# untitled.net
KiCad netlist of a schematic drawn in EAGLE
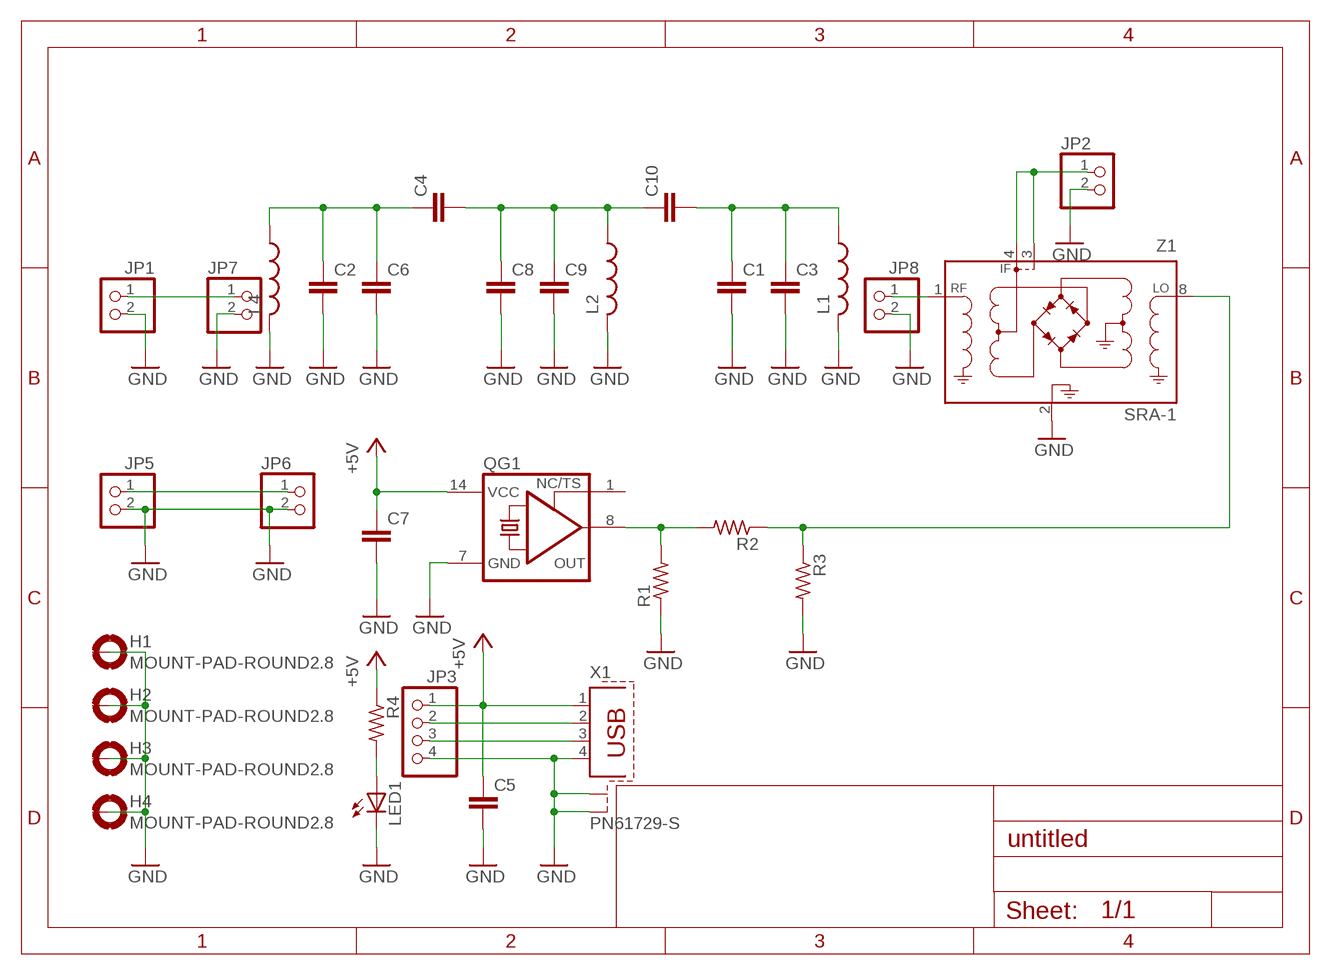
[diagram p0: schematic, sheet 1]

(export (version "E")
  (design (tool "Eeschema 10.0.6"))
  (components
    (comp (ref "C1")
      (value "C5/2.5")
      (footprint "eagle-import:C5B2.5")
      (libsource (lib "eagle-import") (part "C5/2.5"))
    )
    (comp (ref "C2")
      (value "C5/2.5")
      (footprint "eagle-import:C5B2.5")
      (libsource (lib "eagle-import") (part "C5/2.5"))
    )
    (comp (ref "C3")
      (value "C5/2.5")
      (footprint "eagle-import:C5B2.5")
      (libsource (lib "eagle-import") (part "C5/2.5"))
    )
    (comp (ref "C4")
      (value "C5/2.5")
      (footprint "eagle-import:C5B2.5")
      (libsource (lib "eagle-import") (part "C5/2.5"))
    )
    (comp (ref "C5")
      (value "C5/2.5")
      (footprint "eagle-import:C5B2.5")
      (libsource (lib "eagle-import") (part "C5/2.5"))
    )
    (comp (ref "C6")
      (value "C5/2.5")
      (footprint "eagle-import:C5B2.5")
      (libsource (lib "eagle-import") (part "C5/2.5"))
    )
    (comp (ref "C7")
      (value "C5/2.5")
      (footprint "eagle-import:C5B2.5")
      (libsource (lib "eagle-import") (part "C5/2.5"))
    )
    (comp (ref "C8")
      (value "C5/2.5")
      (footprint "eagle-import:C5B2.5")
      (libsource (lib "eagle-import") (part "C5/2.5"))
    )
    (comp (ref "C9")
      (value "C5/2.5")
      (footprint "eagle-import:C5B2.5")
      (libsource (lib "eagle-import") (part "C5/2.5"))
    )
    (comp (ref "C10")
      (value "C5/2.5")
      (footprint "eagle-import:C5B2.5")
      (libsource (lib "eagle-import") (part "C5/2.5"))
    )
    (comp (ref "H1")
      (value "MOUNT-PAD-ROUND2.8")
      (footprint "eagle-import:2,8-PAD")
      (libsource (lib "eagle-import") (part "MOUNT-PAD-ROUND2.8"))
    )
    (comp (ref "H2")
      (value "MOUNT-PAD-ROUND2.8")
      (footprint "eagle-import:2,8-PAD")
      (libsource (lib "eagle-import") (part "MOUNT-PAD-ROUND2.8"))
    )
    (comp (ref "H3")
      (value "MOUNT-PAD-ROUND2.8")
      (footprint "eagle-import:2,8-PAD")
      (libsource (lib "eagle-import") (part "MOUNT-PAD-ROUND2.8"))
    )
    (comp (ref "H4")
      (value "MOUNT-PAD-ROUND2.8")
      (footprint "eagle-import:2,8-PAD")
      (libsource (lib "eagle-import") (part "MOUNT-PAD-ROUND2.8"))
    )
    (comp (ref "JP1")
      (value "PINHD-1X2")
      (footprint "eagle-import:1X02")
      (libsource (lib "eagle-import") (part "PINHD-1X2"))
    )
    (comp (ref "JP2")
      (value "PINHD-1X2")
      (footprint "eagle-import:1X02")
      (libsource (lib "eagle-import") (part "PINHD-1X2"))
    )
    (comp (ref "JP3")
      (value "PINHD-1X4")
      (footprint "eagle-import:1X04")
      (libsource (lib "eagle-import") (part "PINHD-1X4"))
    )
    (comp (ref "JP5")
      (value "PINHD-1X2")
      (footprint "eagle-import:1X02")
      (libsource (lib "eagle-import") (part "PINHD-1X2"))
    )
    (comp (ref "JP6")
      (value "PINHD-1X2")
      (footprint "eagle-import:1X02")
      (libsource (lib "eagle-import") (part "PINHD-1X2"))
    )
    (comp (ref "JP7")
      (value "PINHD-1X2")
      (footprint "eagle-import:1X02")
      (libsource (lib "eagle-import") (part "PINHD-1X2"))
    )
    (comp (ref "JP8")
      (value "PINHD-1X2")
      (footprint "eagle-import:1X02")
      (libsource (lib "eagle-import") (part "PINHD-1X2"))
    )
    (comp (ref "L1")
      (value "L-US0207/7")
      (footprint "eagle-import:0207_7")
      (libsource (lib "eagle-import") (part "L-US0207/7"))
    )
    (comp (ref "L2")
      (value "L-US0207/7")
      (footprint "eagle-import:0207_7")
      (libsource (lib "eagle-import") (part "L-US0207/7"))
    )
    (comp (ref "L4")
      (value "L-US0207/7")
      (footprint "eagle-import:0207_7")
      (libsource (lib "eagle-import") (part "L-US0207/7"))
    )
    (comp (ref "LED1")
      (value "LED3MM")
      (footprint "eagle-import:LED3MM")
      (libsource (lib "eagle-import") (part "LED3MM"))
    )
    (comp (ref "QG1")
      (value "XO-14")
      (footprint "eagle-import:DIL14S")
      (libsource (lib "eagle-import") (part "XO-14"))
    )
    (comp (ref "R1")
      (value "R-US_0207/7")
      (footprint "eagle-import:0207_7")
      (libsource (lib "eagle-import") (part "R-US_0207/7"))
    )
    (comp (ref "R2")
      (value "R-US_0207/7")
      (footprint "eagle-import:0207_7")
      (libsource (lib "eagle-import") (part "R-US_0207/7"))
    )
    (comp (ref "R3")
      (value "R-US_0207/7")
      (footprint "eagle-import:0207_7")
      (libsource (lib "eagle-import") (part "R-US_0207/7"))
    )
    (comp (ref "R4")
      (value "R-US_0207/7")
      (footprint "eagle-import:0207_7")
      (libsource (lib "eagle-import") (part "R-US_0207/7"))
    )
    (comp (ref "X1")
      (value "PN61729-S")
      (footprint "eagle-import:PN61729-S")
      (libsource (lib "eagle-import") (part "PN61729-S"))
    )
    (comp (ref "Z1")
      (value "SRA-1")
      (footprint "eagle-import:A01")
      (libsource (lib "eagle-import") (part "SRA-1"))
    )
  )
  (nets
    (net (code "1") (name "+5V") (class "Default")
      (node (ref "C5") (pin "1") (pinfunction "1_1") (pintype "passive"))
      (node (ref "C7") (pin "1") (pinfunction "1_1") (pintype "passive"))
      (node (ref "JP3") (pin "1") (pinfunction "1_1") (pintype "passive"))
      (node (ref "QG1") (pin "14") (pinfunction "VCC_14") (pintype "power_in"))
      (node (ref "R4") (pin "1") (pinfunction "1_1") (pintype "passive"))
      (node (ref "X1") (pin "1") (pinfunction "1_1") (pintype "passive"))
    )
    (net (code "2") (name "GND") (class "Default")
      (node (ref "C1") (pin "2") (pinfunction "2_2") (pintype "passive"))
      (node (ref "C2") (pin "2") (pinfunction "2_2") (pintype "passive"))
      (node (ref "C3") (pin "2") (pinfunction "2_2") (pintype "passive"))
      (node (ref "C5") (pin "2") (pinfunction "2_2") (pintype "passive"))
      (node (ref "C6") (pin "2") (pinfunction "2_2") (pintype "passive"))
      (node (ref "C7") (pin "2") (pinfunction "2_2") (pintype "passive"))
      (node (ref "C8") (pin "2") (pinfunction "2_2") (pintype "passive"))
      (node (ref "C9") (pin "2") (pinfunction "2_2") (pintype "passive"))
      (node (ref "JP1") (pin "2") (pinfunction "2_2") (pintype "passive"))
      (node (ref "JP2") (pin "2") (pinfunction "2_2") (pintype "passive"))
      (node (ref "JP3") (pin "4") (pinfunction "4_4") (pintype "passive"))
      (node (ref "JP5") (pin "2") (pinfunction "2_2") (pintype "passive"))
      (node (ref "JP6") (pin "2") (pinfunction "2_2") (pintype "passive"))
      (node (ref "JP7") (pin "2") (pinfunction "2_2") (pintype "passive"))
      (node (ref "JP8") (pin "2") (pinfunction "2_2") (pintype "passive"))
      (node (ref "L1") (pin "2") (pinfunction "2_2") (pintype "passive"))
      (node (ref "L2") (pin "2") (pinfunction "2_2") (pintype "passive"))
      (node (ref "L4") (pin "2") (pinfunction "2_2") (pintype "passive"))
      (node (ref "LED1") (pin "K") (pinfunction "C_K") (pintype "passive"))
      (node (ref "QG1") (pin "7") (pinfunction "GND_7") (pintype "power_in"))
      (node (ref "R1") (pin "1") (pinfunction "1_1") (pintype "passive"))
      (node (ref "R3") (pin "2") (pinfunction "2_2") (pintype "passive"))
      (node (ref "X1") (pin "4") (pinfunction "4_4") (pintype "passive"))
      (node (ref "X1") (pin "S1") (pinfunction "S1_S1") (pintype "passive"))
      (node (ref "X1") (pin "S2") (pinfunction "S2_S2") (pintype "passive"))
      (node (ref "Z1") (pin "2") (pinfunction "CASEGROUND_2") (pintype "passive"))
    )
    (net (code "3") (name "Net-(C1-Pad1)") (class "Default")
      (node (ref "C1") (pin "1") (pinfunction "1_1") (pintype "passive"))
      (node (ref "C10") (pin "2") (pinfunction "2_2") (pintype "passive"))
      (node (ref "C3") (pin "1") (pinfunction "1_1") (pintype "passive"))
      (node (ref "L1") (pin "1") (pinfunction "1_1") (pintype "passive"))
    )
    (net (code "4") (name "Net-(C2-Pad1)") (class "Default")
      (node (ref "C2") (pin "1") (pinfunction "1_1") (pintype "passive"))
      (node (ref "C4") (pin "1") (pinfunction "1_1") (pintype "passive"))
      (node (ref "C6") (pin "1") (pinfunction "1_1") (pintype "passive"))
      (node (ref "L4") (pin "1") (pinfunction "1_1") (pintype "passive"))
    )
    (net (code "5") (name "Net-(C10-Pad1)") (class "Default")
      (node (ref "C10") (pin "1") (pinfunction "1_1") (pintype "passive"))
      (node (ref "C4") (pin "2") (pinfunction "2_2") (pintype "passive"))
      (node (ref "C8") (pin "1") (pinfunction "1_1") (pintype "passive"))
      (node (ref "C9") (pin "1") (pinfunction "1_1") (pintype "passive"))
      (node (ref "L2") (pin "1") (pinfunction "1_1") (pintype "passive"))
    )
    (net (code "6") (name "Net-(JP1-Pad1)") (class "Default")
      (node (ref "JP1") (pin "1") (pinfunction "1_1") (pintype "passive"))
      (node (ref "JP7") (pin "1") (pinfunction "1_1") (pintype "passive"))
    )
    (net (code "7") (name "Net-(JP2-Pad1)") (class "Default")
      (node (ref "JP2") (pin "1") (pinfunction "1_1") (pintype "passive"))
      (node (ref "Z1") (pin "3") (pinfunction "IF_3") (pintype "passive"))
      (node (ref "Z1") (pin "4") (pinfunction "IF_4") (pintype "passive"))
    )
    (net (code "8") (name "Net-(JP3-Pad2)") (class "Default")
      (node (ref "JP3") (pin "2") (pinfunction "2_2") (pintype "passive"))
      (node (ref "X1") (pin "2") (pinfunction "2_2") (pintype "passive"))
    )
    (net (code "9") (name "Net-(JP3-Pad3)") (class "Default")
      (node (ref "JP3") (pin "3") (pinfunction "3_3") (pintype "passive"))
      (node (ref "X1") (pin "3") (pinfunction "3_3") (pintype "passive"))
    )
    (net (code "10") (name "Net-(JP5-Pad1)") (class "Default")
      (node (ref "JP5") (pin "1") (pinfunction "1_1") (pintype "passive"))
      (node (ref "JP6") (pin "1") (pinfunction "1_1") (pintype "passive"))
    )
    (net (code "11") (name "Net-(LED1-PadA)") (class "Default")
      (node (ref "LED1") (pin "A") (pinfunction "A_A") (pintype "passive"))
      (node (ref "R4") (pin "2") (pinfunction "2_2") (pintype "passive"))
    )
    (net (code "12") (name "Net-(QG1-OUT)") (class "Default")
      (node (ref "QG1") (pin "8") (pinfunction "OUT_8") (pintype "output"))
      (node (ref "R1") (pin "2") (pinfunction "2_2") (pintype "passive"))
      (node (ref "R2") (pin "2") (pinfunction "2_2") (pintype "passive"))
    )
    (net (code "13") (name "Net-(Z1A-L)") (class "Default")
      (node (ref "R2") (pin "1") (pinfunction "1_1") (pintype "passive"))
      (node (ref "R3") (pin "1") (pinfunction "1_1") (pintype "passive"))
      (node (ref "Z1") (pin "8") (pinfunction "L_8") (pintype "passive"))
    )
    (net (code "14") (name "Net-(Z1A-R)") (class "Default")
      (node (ref "JP8") (pin "1") (pinfunction "1_1") (pintype "passive"))
      (node (ref "Z1") (pin "1") (pinfunction "R_1") (pintype "passive"))
    )
    (net (code "15") (name "unconnected-(H1-MOUNT-PadB2,8)") (class "Default")
      (node (ref "H1") (pin "B2,8") (pinfunction "MOUNT_B2,8") (pintype "passive"))
    )
    (net (code "16") (name "unconnected-(H2-MOUNT-PadB2,8)") (class "Default")
      (node (ref "H2") (pin "B2,8") (pinfunction "MOUNT_B2,8") (pintype "passive"))
    )
    (net (code "17") (name "unconnected-(H3-MOUNT-PadB2,8)") (class "Default")
      (node (ref "H3") (pin "B2,8") (pinfunction "MOUNT_B2,8") (pintype "passive"))
    )
    (net (code "18") (name "unconnected-(H4-MOUNT-PadB2,8)") (class "Default")
      (node (ref "H4") (pin "B2,8") (pinfunction "MOUNT_B2,8") (pintype "passive"))
    )
    (net (code "19") (name "unconnected-(QG1-TS-Pad1)") (class "Default")
      (node (ref "QG1") (pin "1") (pinfunction "TS_1") (pintype "passive"))
    )
  )
)
